# MICRO_SQUARED_SENSING.net
KiCad netlist of a schematic drawn in EAGLE
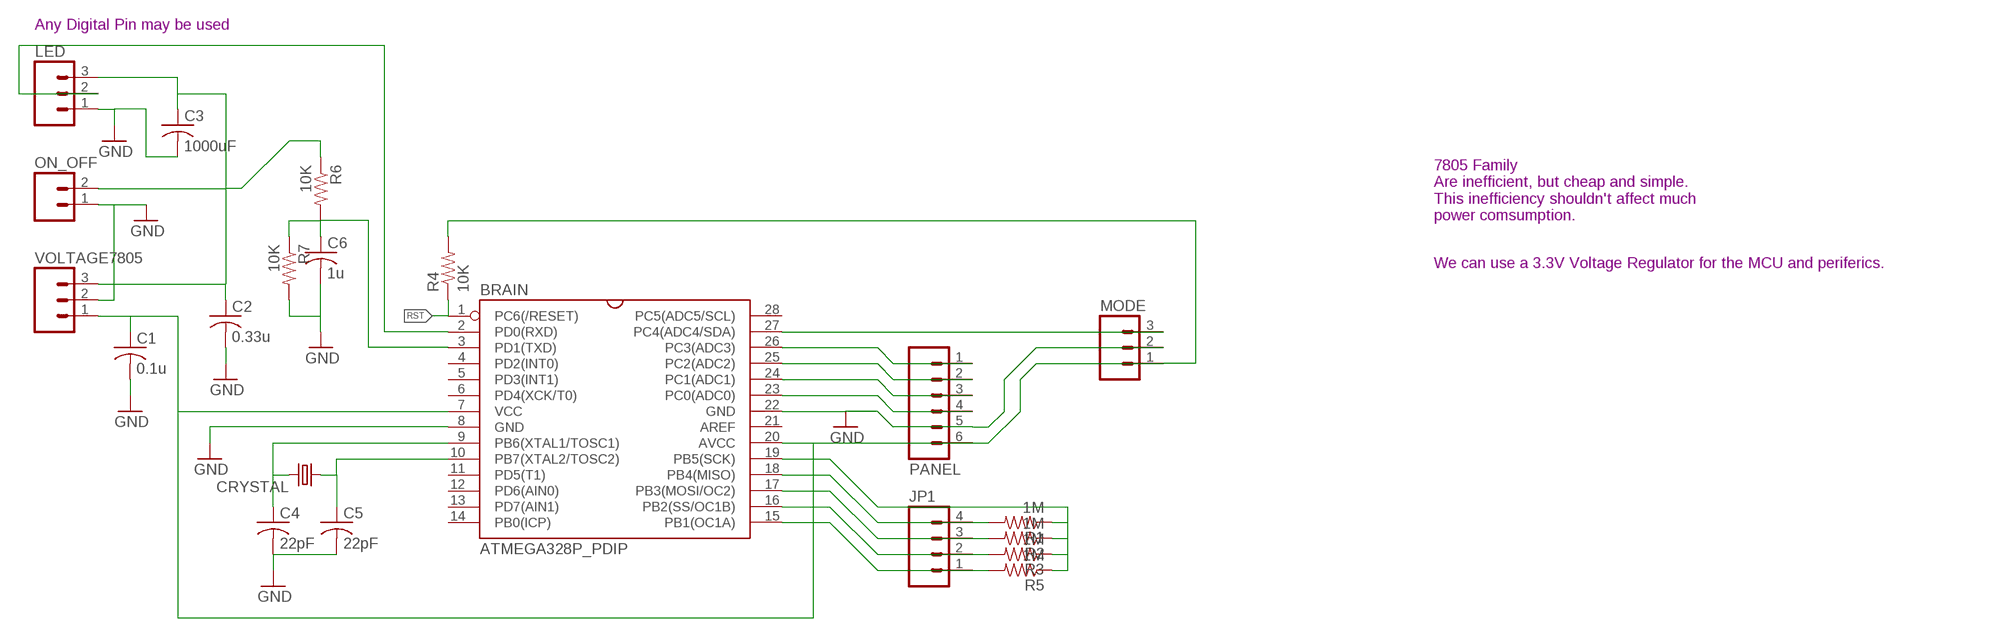
[diagram p0: schematic, sheet 1]

(export (version "E")
  (design (tool "Eeschema 10.0.6"))
  (components
    (comp (ref "BRAIN")
      (value "ATMEGA328P_PDIP")
      (footprint "eagle-import:DIL-28-3")
      (libsource (lib "eagle-import") (part "ATMEGA328P_PDIP"))
    )
    (comp (ref "C1")
      (value "0.1u")
      (footprint "eagle-import:C025-025X050")
      (libsource (lib "eagle-import") (part "C-US025-025X050"))
    )
    (comp (ref "C2")
      (value "0.33u")
      (footprint "eagle-import:C025-025X050")
      (libsource (lib "eagle-import") (part "C-US025-025X050"))
    )
    (comp (ref "C3")
      (value "1000uF")
      (footprint "eagle-import:C050-075X075")
      (libsource (lib "eagle-import") (part "C-US050-075X075"))
    )
    (comp (ref "C4")
      (value "22pF")
      (footprint "eagle-import:C025-024X044")
      (libsource (lib "eagle-import") (part "C-US025-024X044"))
    )
    (comp (ref "C5")
      (value "22pF")
      (footprint "eagle-import:C025-024X044")
      (libsource (lib "eagle-import") (part "C-US025-024X044"))
    )
    (comp (ref "C6")
      (value "1u")
      (footprint "eagle-import:C025-025X050")
      (libsource (lib "eagle-import") (part "C-US025-025X050"))
    )
    (comp (ref "CRYSTAL")
      (value "CRYSTALHC49US")
      (footprint "eagle-import:HC49US")
      (libsource (lib "eagle-import") (part "CRYSTALHC49US"))
    )
    (comp (ref "JP1")
      (value "M04PTH")
      (footprint "eagle-import:1X04")
      (libsource (lib "eagle-import") (part "M04PTH"))
    )
    (comp (ref "LED")
      (value "M03PTH")
      (footprint "eagle-import:1X03")
      (libsource (lib "eagle-import") (part "M03PTH"))
    )
    (comp (ref "MODE")
      (value "M03PTH")
      (footprint "eagle-import:1X03")
      (libsource (lib "eagle-import") (part "M03PTH"))
    )
    (comp (ref "ON_OFF")
      (value "M02PTH")
      (footprint "eagle-import:1X02")
      (libsource (lib "eagle-import") (part "M02PTH"))
    )
    (comp (ref "PANEL")
      (value "M06NO_SILK_FEMALE_PTH")
      (footprint "eagle-import:1X06_NO_SILK")
      (libsource (lib "eagle-import") (part "M06NO_SILK_FEMALE_PTH"))
    )
    (comp (ref "R1")
      (value "1M")
      (footprint "eagle-import:AXIAL-0.3")
      (libsource (lib "eagle-import") (part "RESISTORAXIAL-0.3"))
    )
    (comp (ref "R2")
      (value "1M")
      (footprint "eagle-import:AXIAL-0.3")
      (libsource (lib "eagle-import") (part "RESISTORAXIAL-0.3"))
    )
    (comp (ref "R3")
      (value "1M")
      (footprint "eagle-import:AXIAL-0.3")
      (libsource (lib "eagle-import") (part "RESISTORAXIAL-0.3"))
    )
    (comp (ref "R4")
      (value "10K")
      (footprint "eagle-import:AXIAL-0.3")
      (libsource (lib "eagle-import") (part "RESISTORAXIAL-0.3"))
    )
    (comp (ref "R5")
      (value "1M")
      (footprint "eagle-import:AXIAL-0.3")
      (libsource (lib "eagle-import") (part "RESISTORAXIAL-0.3"))
    )
    (comp (ref "R6")
      (value "10K")
      (footprint "eagle-import:AXIAL-0.3")
      (libsource (lib "eagle-import") (part "RESISTORAXIAL-0.3"))
    )
    (comp (ref "R7")
      (value "10K")
      (footprint "eagle-import:AXIAL-0.3")
      (libsource (lib "eagle-import") (part "RESISTORAXIAL-0.3"))
    )
    (comp (ref "VOLTAGE7805")
      (value "M03PTH")
      (footprint "eagle-import:1X03")
      (libsource (lib "eagle-import") (part "M03PTH"))
    )
  )
  (nets
    (net (code "1") (name "GND") (class "Default")
      (node (ref "BRAIN") (pin "22") (pinfunction "GND_22") (pintype "bidirectional"))
      (node (ref "BRAIN") (pin "8") (pinfunction "GND_8") (pintype "bidirectional"))
      (node (ref "C1") (pin "2") (pinfunction "2_2") (pintype "passive"))
      (node (ref "C2") (pin "2") (pinfunction "2_2") (pintype "passive"))
      (node (ref "C3") (pin "2") (pinfunction "2_2") (pintype "passive"))
      (node (ref "C4") (pin "2") (pinfunction "2_2") (pintype "passive"))
      (node (ref "C5") (pin "2") (pinfunction "2_2") (pintype "passive"))
      (node (ref "C6") (pin "2") (pinfunction "2_2") (pintype "passive"))
      (node (ref "LED") (pin "1") (pinfunction "1_1") (pintype "passive"))
      (node (ref "MODE") (pin "2") (pinfunction "2_2") (pintype "passive"))
      (node (ref "ON_OFF") (pin "1") (pinfunction "1_1") (pintype "passive"))
      (node (ref "PANEL") (pin "5") (pinfunction "5_5") (pintype "passive"))
      (node (ref "R7") (pin "P$2") (pinfunction "2_P$2") (pintype "passive"))
      (node (ref "VOLTAGE7805") (pin "2") (pinfunction "2_2") (pintype "passive"))
    )
    (net (code "2") (name "Net-(BRAIN-AVCC)") (class "Default")
      (node (ref "BRAIN") (pin "20") (pinfunction "AVCC_20") (pintype "bidirectional"))
      (node (ref "BRAIN") (pin "7") (pinfunction "VCC_7") (pintype "bidirectional"))
      (node (ref "C1") (pin "1") (pinfunction "1_1") (pintype "passive"))
      (node (ref "MODE") (pin "1") (pinfunction "1_1") (pintype "passive"))
      (node (ref "PANEL") (pin "6") (pinfunction "6_6") (pintype "passive"))
      (node (ref "R4") (pin "P$2") (pinfunction "2_P$2") (pintype "passive"))
      (node (ref "VOLTAGE7805") (pin "1") (pinfunction "1_1") (pintype "passive"))
    )
    (net (code "3") (name "Net-(BRAIN-PB1(OC1A))") (class "Default")
      (node (ref "BRAIN") (pin "15") (pinfunction "PB1(OC1A)_15") (pintype "bidirectional"))
      (node (ref "JP1") (pin "1") (pinfunction "1_1") (pintype "passive"))
      (node (ref "R5") (pin "P$2") (pinfunction "2_P$2") (pintype "passive"))
    )
    (net (code "4") (name "Net-(BRAIN-PB2(SS{slash}OC1B))") (class "Default")
      (node (ref "BRAIN") (pin "16") (pinfunction "PB2(SS/OC1B)_16") (pintype "bidirectional"))
      (node (ref "JP1") (pin "2") (pinfunction "2_2") (pintype "passive"))
      (node (ref "R3") (pin "P$2") (pinfunction "2_P$2") (pintype "passive"))
    )
    (net (code "5") (name "Net-(BRAIN-PB3(MOSI{slash}OC2))") (class "Default")
      (node (ref "BRAIN") (pin "17") (pinfunction "PB3(MOSI/OC2)_17") (pintype "bidirectional"))
      (node (ref "JP1") (pin "3") (pinfunction "3_3") (pintype "passive"))
      (node (ref "R2") (pin "P$2") (pinfunction "2_P$2") (pintype "passive"))
    )
    (net (code "6") (name "Net-(BRAIN-PB4(MISO))") (class "Default")
      (node (ref "BRAIN") (pin "18") (pinfunction "PB4(MISO)_18") (pintype "bidirectional"))
      (node (ref "JP1") (pin "4") (pinfunction "4_4") (pintype "passive"))
      (node (ref "R1") (pin "P$2") (pinfunction "2_P$2") (pintype "passive"))
    )
    (net (code "7") (name "Net-(BRAIN-PB5(SCK))") (class "Default")
      (node (ref "BRAIN") (pin "19") (pinfunction "PB5(SCK)_19") (pintype "bidirectional"))
      (node (ref "R1") (pin "P$1") (pinfunction "1_P$1") (pintype "passive"))
      (node (ref "R2") (pin "P$1") (pinfunction "1_P$1") (pintype "passive"))
      (node (ref "R3") (pin "P$1") (pinfunction "1_P$1") (pintype "passive"))
      (node (ref "R5") (pin "P$1") (pinfunction "1_P$1") (pintype "passive"))
    )
    (net (code "8") (name "Net-(BRAIN-PB6(XTAL1{slash}TOSC1))") (class "Default")
      (node (ref "BRAIN") (pin "9") (pinfunction "PB6(XTAL1/TOSC1)_9") (pintype "bidirectional"))
      (node (ref "C4") (pin "1") (pinfunction "1_1") (pintype "passive"))
      (node (ref "CRYSTAL") (pin "2") (pinfunction "2_2") (pintype "passive"))
    )
    (net (code "9") (name "Net-(BRAIN-PB7(XTAL2{slash}TOSC2))") (class "Default")
      (node (ref "BRAIN") (pin "10") (pinfunction "PB7(XTAL2/TOSC2)_10") (pintype "bidirectional"))
      (node (ref "C5") (pin "1") (pinfunction "1_1") (pintype "passive"))
      (node (ref "CRYSTAL") (pin "1") (pinfunction "1_1") (pintype "passive"))
    )
    (net (code "10") (name "Net-(BRAIN-PC0(ADC0))") (class "Default")
      (node (ref "BRAIN") (pin "23") (pinfunction "PC0(ADC0)_23") (pintype "bidirectional"))
      (node (ref "PANEL") (pin "4") (pinfunction "4_4") (pintype "passive"))
    )
    (net (code "11") (name "Net-(BRAIN-PC1(ADC1))") (class "Default")
      (node (ref "BRAIN") (pin "24") (pinfunction "PC1(ADC1)_24") (pintype "bidirectional"))
      (node (ref "PANEL") (pin "3") (pinfunction "3_3") (pintype "passive"))
    )
    (net (code "12") (name "Net-(BRAIN-PC2(ADC2))") (class "Default")
      (node (ref "BRAIN") (pin "25") (pinfunction "PC2(ADC2)_25") (pintype "bidirectional"))
      (node (ref "PANEL") (pin "2") (pinfunction "2_2") (pintype "passive"))
    )
    (net (code "13") (name "Net-(BRAIN-PC3(ADC3))") (class "Default")
      (node (ref "BRAIN") (pin "26") (pinfunction "PC3(ADC3)_26") (pintype "bidirectional"))
      (node (ref "PANEL") (pin "1") (pinfunction "1_1") (pintype "passive"))
    )
    (net (code "14") (name "Net-(BRAIN-PC4(ADC4{slash}SDA))") (class "Default")
      (node (ref "BRAIN") (pin "27") (pinfunction "PC4(ADC4/SDA)_27") (pintype "bidirectional"))
      (node (ref "MODE") (pin "3") (pinfunction "3_3") (pintype "passive"))
    )
    (net (code "15") (name "Net-(BRAIN-PD0(RXD))") (class "Default")
      (node (ref "BRAIN") (pin "2") (pinfunction "PD0(RXD)_2") (pintype "bidirectional"))
      (node (ref "LED") (pin "2") (pinfunction "2_2") (pintype "passive"))
    )
    (net (code "16") (name "Net-(BRAIN-PD1(TXD))") (class "Default")
      (node (ref "BRAIN") (pin "3") (pinfunction "PD1(TXD)_3") (pintype "bidirectional"))
      (node (ref "C6") (pin "1") (pinfunction "1_1") (pintype "passive"))
      (node (ref "R6") (pin "P$2") (pinfunction "2_P$2") (pintype "passive"))
      (node (ref "R7") (pin "P$1") (pinfunction "1_P$1") (pintype "passive"))
    )
    (net (code "17") (name "Net-(R6-1)") (class "Default")
      (node (ref "C2") (pin "1") (pinfunction "1_1") (pintype "passive"))
      (node (ref "C3") (pin "1") (pinfunction "1_1") (pintype "passive"))
      (node (ref "LED") (pin "3") (pinfunction "3_3") (pintype "passive"))
      (node (ref "ON_OFF") (pin "2") (pinfunction "2_2") (pintype "passive"))
      (node (ref "R6") (pin "P$1") (pinfunction "1_P$1") (pintype "passive"))
      (node (ref "VOLTAGE7805") (pin "3") (pinfunction "3_3") (pintype "passive"))
    )
    (net (code "18") (name "RST") (class "Default")
      (node (ref "BRAIN") (pin "1") (pinfunction "PC6(/RESET)_1") (pintype "bidirectional"))
      (node (ref "R4") (pin "P$1") (pinfunction "1_P$1") (pintype "passive"))
    )
    (net (code "19") (name "unconnected-(BRAIN-AREF-Pad21)") (class "Default")
      (node (ref "BRAIN") (pin "21") (pinfunction "AREF_21") (pintype "bidirectional"))
    )
    (net (code "20") (name "unconnected-(BRAIN-PB0(ICP)-Pad14)") (class "Default")
      (node (ref "BRAIN") (pin "14") (pinfunction "PB0(ICP)_14") (pintype "bidirectional"))
    )
    (net (code "21") (name "unconnected-(BRAIN-PC5(ADC5{slash}SCL)-Pad28)") (class "Default")
      (node (ref "BRAIN") (pin "28") (pinfunction "PC5(ADC5/SCL)_28") (pintype "bidirectional"))
    )
    (net (code "22") (name "unconnected-(BRAIN-PD2(INT0)-Pad4)") (class "Default")
      (node (ref "BRAIN") (pin "4") (pinfunction "PD2(INT0)_4") (pintype "bidirectional"))
    )
    (net (code "23") (name "unconnected-(BRAIN-PD3(INT1)-Pad5)") (class "Default")
      (node (ref "BRAIN") (pin "5") (pinfunction "PD3(INT1)_5") (pintype "bidirectional"))
    )
    (net (code "24") (name "unconnected-(BRAIN-PD4(XCK{slash}T0)-Pad6)") (class "Default")
      (node (ref "BRAIN") (pin "6") (pinfunction "PD4(XCK/T0)_6") (pintype "bidirectional"))
    )
    (net (code "25") (name "unconnected-(BRAIN-PD5(T1)-Pad11)") (class "Default")
      (node (ref "BRAIN") (pin "11") (pinfunction "PD5(T1)_11") (pintype "bidirectional"))
    )
    (net (code "26") (name "unconnected-(BRAIN-PD6(AIN0)-Pad12)") (class "Default")
      (node (ref "BRAIN") (pin "12") (pinfunction "PD6(AIN0)_12") (pintype "bidirectional"))
    )
    (net (code "27") (name "unconnected-(BRAIN-PD7(AIN1)-Pad13)") (class "Default")
      (node (ref "BRAIN") (pin "13") (pinfunction "PD7(AIN1)_13") (pintype "bidirectional"))
    )
  )
)
